# SubBus5.net
KiCad netlist of a schematic drawn in Altium Designer
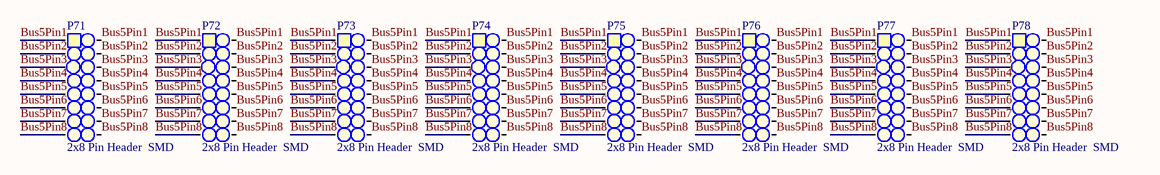
[diagram p0: SubBus5.SchDoc]

(export (version "E")
  (design (tool "Eeschema 10.0.6"))
  (components
    (comp (ref "P71")
      (value "2x8 Pin Header  SMD")
      (footprint "2X8_SMD_PH_2.54")
      (description "2.54mm, SMD")
      (libsource (lib "jclib") (part "2x8 Pin Header  SMD"))
    )
    (comp (ref "P72")
      (value "2x8 Pin Header  SMD")
      (footprint "2X8_SMD_PH_2.54")
      (description "2.54mm, SMD")
      (libsource (lib "jclib") (part "2x8 Pin Header  SMD"))
    )
    (comp (ref "P73")
      (value "2x8 Pin Header  SMD")
      (footprint "2X8_SMD_PH_2.54")
      (description "2.54mm, SMD")
      (libsource (lib "jclib") (part "2x8 Pin Header  SMD"))
    )
    (comp (ref "P74")
      (value "2x8 Pin Header  SMD")
      (footprint "2X8_SMD_PH_2.54")
      (description "2.54mm, SMD")
      (libsource (lib "jclib") (part "2x8 Pin Header  SMD"))
    )
    (comp (ref "P75")
      (value "2x8 Pin Header  SMD")
      (footprint "2X8_SMD_PH_2.54")
      (description "2.54mm, SMD")
      (libsource (lib "jclib") (part "2x8 Pin Header  SMD"))
    )
    (comp (ref "P76")
      (value "2x8 Pin Header  SMD")
      (footprint "2X8_SMD_PH_2.54")
      (description "2.54mm, SMD")
      (libsource (lib "jclib") (part "2x8 Pin Header  SMD"))
    )
    (comp (ref "P77")
      (value "2x8 Pin Header  SMD")
      (footprint "2X8_SMD_PH_2.54")
      (description "2.54mm, SMD")
      (libsource (lib "jclib") (part "2x8 Pin Header  SMD"))
    )
    (comp (ref "P78")
      (value "2x8 Pin Header  SMD")
      (footprint "2X8_SMD_PH_2.54")
      (description "2.54mm, SMD")
      (libsource (lib "jclib") (part "2x8 Pin Header  SMD"))
    )
  )
  (nets
    (net (code "1") (name "/Bus5Pin1") (class "Default")
      (node (ref "P71") (pin "1") (pinfunction "1_1") (pintype "passive"))
      (node (ref "P71") (pin "16") (pinfunction "16_16") (pintype "passive"))
      (node (ref "P72") (pin "1") (pinfunction "1_1") (pintype "passive"))
      (node (ref "P72") (pin "16") (pinfunction "16_16") (pintype "passive"))
      (node (ref "P73") (pin "1") (pinfunction "1_1") (pintype "passive"))
      (node (ref "P73") (pin "16") (pinfunction "16_16") (pintype "passive"))
      (node (ref "P74") (pin "1") (pinfunction "1_1") (pintype "passive"))
      (node (ref "P74") (pin "16") (pinfunction "16_16") (pintype "passive"))
      (node (ref "P75") (pin "1") (pinfunction "1_1") (pintype "passive"))
      (node (ref "P75") (pin "16") (pinfunction "16_16") (pintype "passive"))
      (node (ref "P76") (pin "1") (pinfunction "1_1") (pintype "passive"))
      (node (ref "P76") (pin "16") (pinfunction "16_16") (pintype "passive"))
      (node (ref "P77") (pin "1") (pinfunction "1_1") (pintype "passive"))
      (node (ref "P77") (pin "16") (pinfunction "16_16") (pintype "passive"))
      (node (ref "P78") (pin "1") (pinfunction "1_1") (pintype "passive"))
      (node (ref "P78") (pin "16") (pinfunction "16_16") (pintype "passive"))
    )
    (net (code "2") (name "/Bus5Pin2") (class "Default")
      (node (ref "P71") (pin "15") (pinfunction "15_15") (pintype "passive"))
      (node (ref "P71") (pin "2") (pinfunction "2_2") (pintype "passive"))
      (node (ref "P72") (pin "15") (pinfunction "15_15") (pintype "passive"))
      (node (ref "P72") (pin "2") (pinfunction "2_2") (pintype "passive"))
      (node (ref "P73") (pin "15") (pinfunction "15_15") (pintype "passive"))
      (node (ref "P73") (pin "2") (pinfunction "2_2") (pintype "passive"))
      (node (ref "P74") (pin "15") (pinfunction "15_15") (pintype "passive"))
      (node (ref "P74") (pin "2") (pinfunction "2_2") (pintype "passive"))
      (node (ref "P75") (pin "15") (pinfunction "15_15") (pintype "passive"))
      (node (ref "P75") (pin "2") (pinfunction "2_2") (pintype "passive"))
      (node (ref "P76") (pin "15") (pinfunction "15_15") (pintype "passive"))
      (node (ref "P76") (pin "2") (pinfunction "2_2") (pintype "passive"))
      (node (ref "P77") (pin "15") (pinfunction "15_15") (pintype "passive"))
      (node (ref "P77") (pin "2") (pinfunction "2_2") (pintype "passive"))
      (node (ref "P78") (pin "15") (pinfunction "15_15") (pintype "passive"))
      (node (ref "P78") (pin "2") (pinfunction "2_2") (pintype "passive"))
    )
    (net (code "3") (name "/Bus5Pin3") (class "Default")
      (node (ref "P71") (pin "14") (pinfunction "14_14") (pintype "passive"))
      (node (ref "P71") (pin "3") (pinfunction "3_3") (pintype "passive"))
      (node (ref "P72") (pin "14") (pinfunction "14_14") (pintype "passive"))
      (node (ref "P72") (pin "3") (pinfunction "3_3") (pintype "passive"))
      (node (ref "P73") (pin "14") (pinfunction "14_14") (pintype "passive"))
      (node (ref "P73") (pin "3") (pinfunction "3_3") (pintype "passive"))
      (node (ref "P74") (pin "14") (pinfunction "14_14") (pintype "passive"))
      (node (ref "P74") (pin "3") (pinfunction "3_3") (pintype "passive"))
      (node (ref "P75") (pin "14") (pinfunction "14_14") (pintype "passive"))
      (node (ref "P75") (pin "3") (pinfunction "3_3") (pintype "passive"))
      (node (ref "P76") (pin "14") (pinfunction "14_14") (pintype "passive"))
      (node (ref "P76") (pin "3") (pinfunction "3_3") (pintype "passive"))
      (node (ref "P77") (pin "14") (pinfunction "14_14") (pintype "passive"))
      (node (ref "P77") (pin "3") (pinfunction "3_3") (pintype "passive"))
      (node (ref "P78") (pin "14") (pinfunction "14_14") (pintype "passive"))
      (node (ref "P78") (pin "3") (pinfunction "3_3") (pintype "passive"))
    )
    (net (code "4") (name "/Bus5Pin4") (class "Default")
      (node (ref "P71") (pin "13") (pinfunction "13_13") (pintype "passive"))
      (node (ref "P71") (pin "4") (pinfunction "4_4") (pintype "passive"))
      (node (ref "P72") (pin "13") (pinfunction "13_13") (pintype "passive"))
      (node (ref "P72") (pin "4") (pinfunction "4_4") (pintype "passive"))
      (node (ref "P73") (pin "13") (pinfunction "13_13") (pintype "passive"))
      (node (ref "P73") (pin "4") (pinfunction "4_4") (pintype "passive"))
      (node (ref "P74") (pin "13") (pinfunction "13_13") (pintype "passive"))
      (node (ref "P74") (pin "4") (pinfunction "4_4") (pintype "passive"))
      (node (ref "P75") (pin "13") (pinfunction "13_13") (pintype "passive"))
      (node (ref "P75") (pin "4") (pinfunction "4_4") (pintype "passive"))
      (node (ref "P76") (pin "13") (pinfunction "13_13") (pintype "passive"))
      (node (ref "P76") (pin "4") (pinfunction "4_4") (pintype "passive"))
      (node (ref "P77") (pin "13") (pinfunction "13_13") (pintype "passive"))
      (node (ref "P77") (pin "4") (pinfunction "4_4") (pintype "passive"))
      (node (ref "P78") (pin "13") (pinfunction "13_13") (pintype "passive"))
      (node (ref "P78") (pin "4") (pinfunction "4_4") (pintype "passive"))
    )
    (net (code "5") (name "/Bus5Pin5") (class "Default")
      (node (ref "P71") (pin "12") (pinfunction "12_12") (pintype "passive"))
      (node (ref "P71") (pin "5") (pinfunction "5_5") (pintype "passive"))
      (node (ref "P72") (pin "12") (pinfunction "12_12") (pintype "passive"))
      (node (ref "P72") (pin "5") (pinfunction "5_5") (pintype "passive"))
      (node (ref "P73") (pin "12") (pinfunction "12_12") (pintype "passive"))
      (node (ref "P73") (pin "5") (pinfunction "5_5") (pintype "passive"))
      (node (ref "P74") (pin "12") (pinfunction "12_12") (pintype "passive"))
      (node (ref "P74") (pin "5") (pinfunction "5_5") (pintype "passive"))
      (node (ref "P75") (pin "12") (pinfunction "12_12") (pintype "passive"))
      (node (ref "P75") (pin "5") (pinfunction "5_5") (pintype "passive"))
      (node (ref "P76") (pin "12") (pinfunction "12_12") (pintype "passive"))
      (node (ref "P76") (pin "5") (pinfunction "5_5") (pintype "passive"))
      (node (ref "P77") (pin "12") (pinfunction "12_12") (pintype "passive"))
      (node (ref "P77") (pin "5") (pinfunction "5_5") (pintype "passive"))
      (node (ref "P78") (pin "12") (pinfunction "12_12") (pintype "passive"))
      (node (ref "P78") (pin "5") (pinfunction "5_5") (pintype "passive"))
    )
    (net (code "6") (name "/Bus5Pin6") (class "Default")
      (node (ref "P71") (pin "11") (pinfunction "11_11") (pintype "passive"))
      (node (ref "P71") (pin "6") (pinfunction "6_6") (pintype "passive"))
      (node (ref "P72") (pin "11") (pinfunction "11_11") (pintype "passive"))
      (node (ref "P72") (pin "6") (pinfunction "6_6") (pintype "passive"))
      (node (ref "P73") (pin "11") (pinfunction "11_11") (pintype "passive"))
      (node (ref "P73") (pin "6") (pinfunction "6_6") (pintype "passive"))
      (node (ref "P74") (pin "11") (pinfunction "11_11") (pintype "passive"))
      (node (ref "P74") (pin "6") (pinfunction "6_6") (pintype "passive"))
      (node (ref "P75") (pin "11") (pinfunction "11_11") (pintype "passive"))
      (node (ref "P75") (pin "6") (pinfunction "6_6") (pintype "passive"))
      (node (ref "P76") (pin "11") (pinfunction "11_11") (pintype "passive"))
      (node (ref "P76") (pin "6") (pinfunction "6_6") (pintype "passive"))
      (node (ref "P77") (pin "11") (pinfunction "11_11") (pintype "passive"))
      (node (ref "P77") (pin "6") (pinfunction "6_6") (pintype "passive"))
      (node (ref "P78") (pin "11") (pinfunction "11_11") (pintype "passive"))
      (node (ref "P78") (pin "6") (pinfunction "6_6") (pintype "passive"))
    )
    (net (code "7") (name "/Bus5Pin7") (class "Default")
      (node (ref "P71") (pin "10") (pinfunction "10_10") (pintype "passive"))
      (node (ref "P71") (pin "7") (pinfunction "7_7") (pintype "passive"))
      (node (ref "P72") (pin "10") (pinfunction "10_10") (pintype "passive"))
      (node (ref "P72") (pin "7") (pinfunction "7_7") (pintype "passive"))
      (node (ref "P73") (pin "10") (pinfunction "10_10") (pintype "passive"))
      (node (ref "P73") (pin "7") (pinfunction "7_7") (pintype "passive"))
      (node (ref "P74") (pin "10") (pinfunction "10_10") (pintype "passive"))
      (node (ref "P74") (pin "7") (pinfunction "7_7") (pintype "passive"))
      (node (ref "P75") (pin "10") (pinfunction "10_10") (pintype "passive"))
      (node (ref "P75") (pin "7") (pinfunction "7_7") (pintype "passive"))
      (node (ref "P76") (pin "10") (pinfunction "10_10") (pintype "passive"))
      (node (ref "P76") (pin "7") (pinfunction "7_7") (pintype "passive"))
      (node (ref "P77") (pin "10") (pinfunction "10_10") (pintype "passive"))
      (node (ref "P77") (pin "7") (pinfunction "7_7") (pintype "passive"))
      (node (ref "P78") (pin "10") (pinfunction "10_10") (pintype "passive"))
      (node (ref "P78") (pin "7") (pinfunction "7_7") (pintype "passive"))
    )
    (net (code "8") (name "/Bus5Pin8") (class "Default")
      (node (ref "P71") (pin "8") (pinfunction "8_8") (pintype "passive"))
      (node (ref "P71") (pin "9") (pinfunction "9_9") (pintype "passive"))
      (node (ref "P72") (pin "8") (pinfunction "8_8") (pintype "passive"))
      (node (ref "P72") (pin "9") (pinfunction "9_9") (pintype "passive"))
      (node (ref "P73") (pin "8") (pinfunction "8_8") (pintype "passive"))
      (node (ref "P73") (pin "9") (pinfunction "9_9") (pintype "passive"))
      (node (ref "P74") (pin "8") (pinfunction "8_8") (pintype "passive"))
      (node (ref "P74") (pin "9") (pinfunction "9_9") (pintype "passive"))
      (node (ref "P75") (pin "8") (pinfunction "8_8") (pintype "passive"))
      (node (ref "P75") (pin "9") (pinfunction "9_9") (pintype "passive"))
      (node (ref "P76") (pin "8") (pinfunction "8_8") (pintype "passive"))
      (node (ref "P76") (pin "9") (pinfunction "9_9") (pintype "passive"))
      (node (ref "P77") (pin "8") (pinfunction "8_8") (pintype "passive"))
      (node (ref "P77") (pin "9") (pinfunction "9_9") (pintype "passive"))
      (node (ref "P78") (pin "8") (pinfunction "8_8") (pintype "passive"))
      (node (ref "P78") (pin "9") (pinfunction "9_9") (pintype "passive"))
    )
  )
)
